# Sensor_Board_v2_4_1_2_N.net
KiCad netlist of a schematic drawn in EAGLE
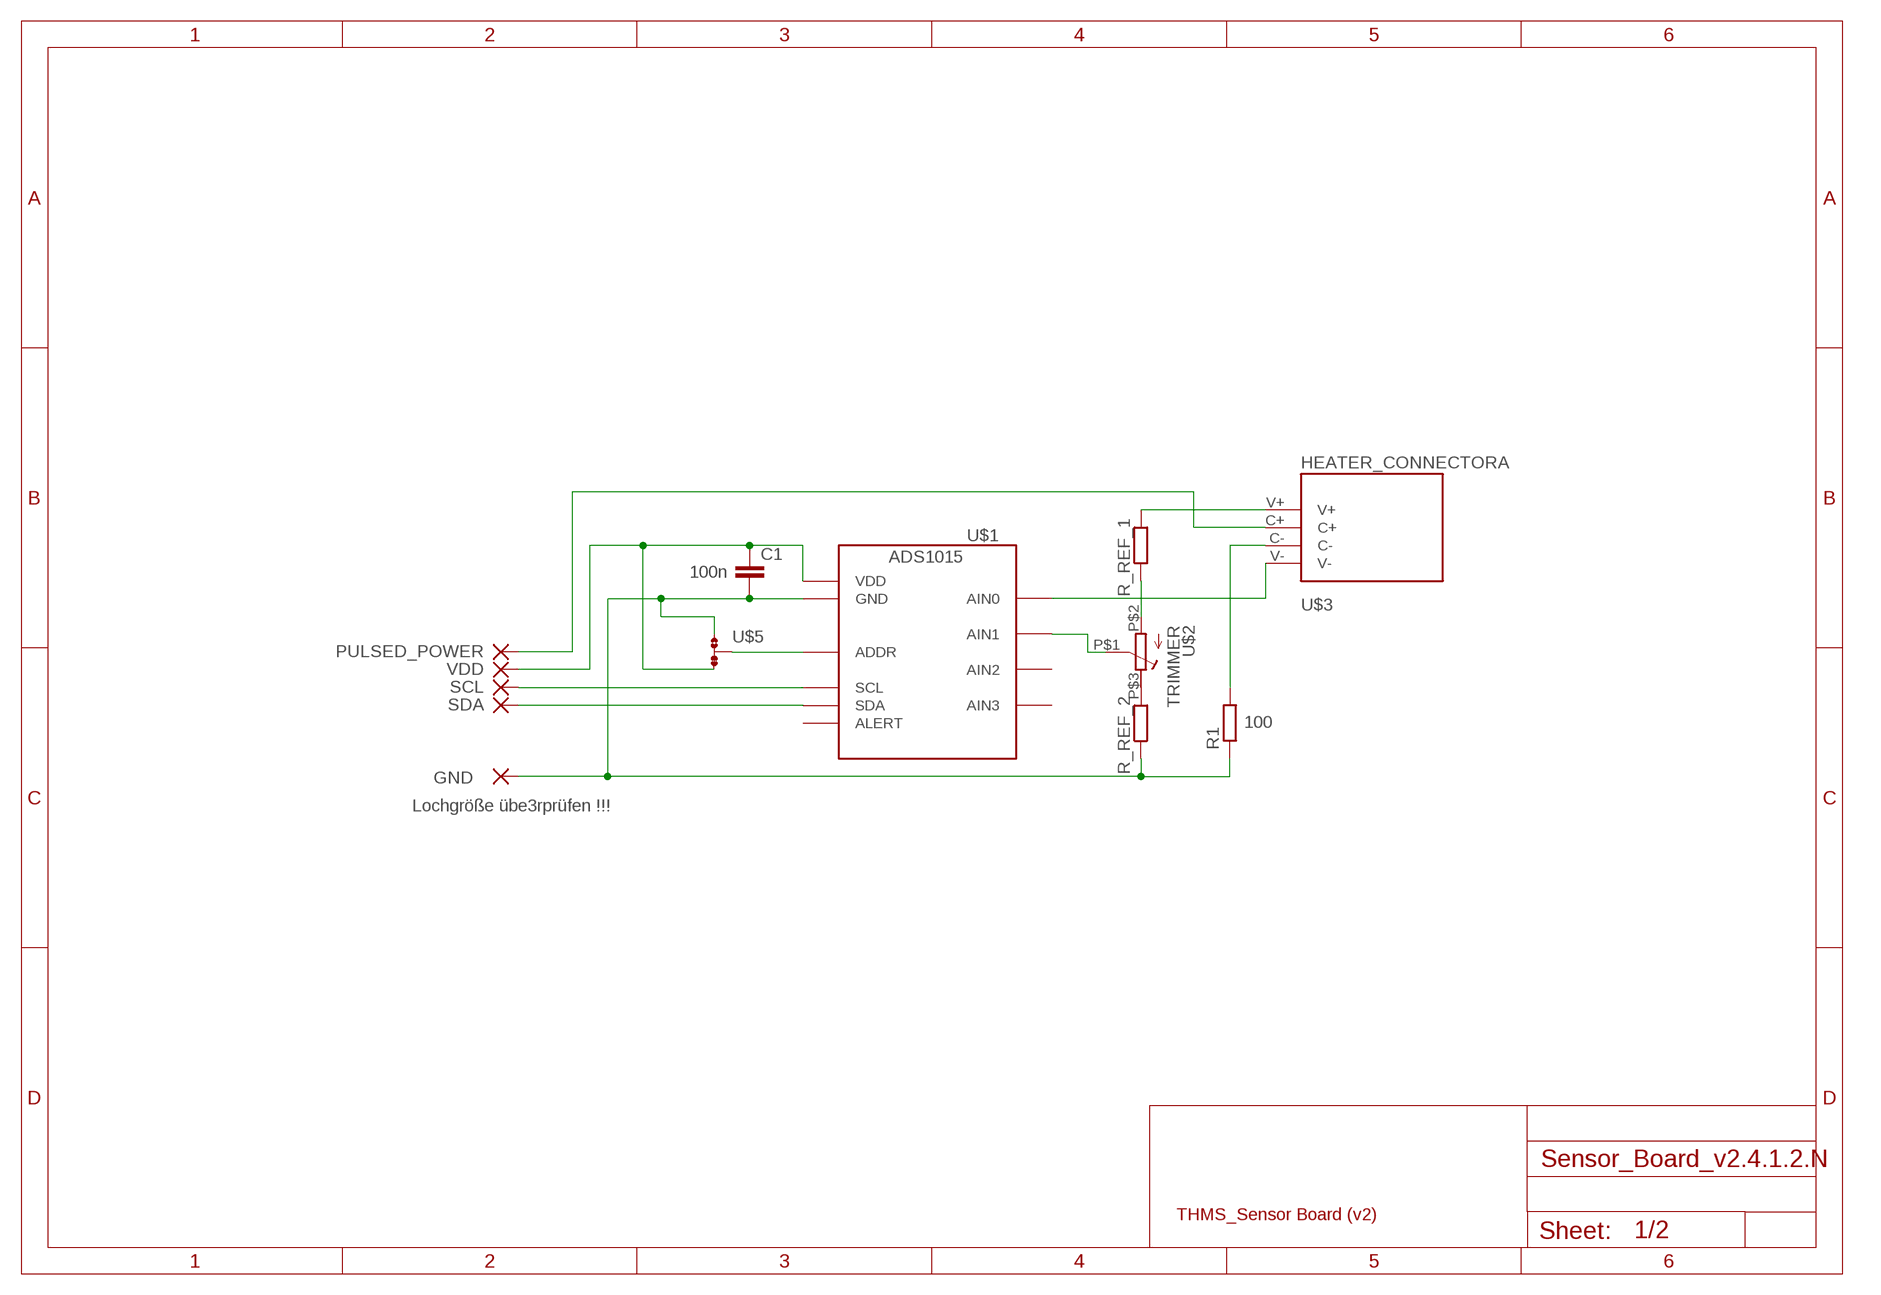
[diagram p0: schematic, sheet 1]
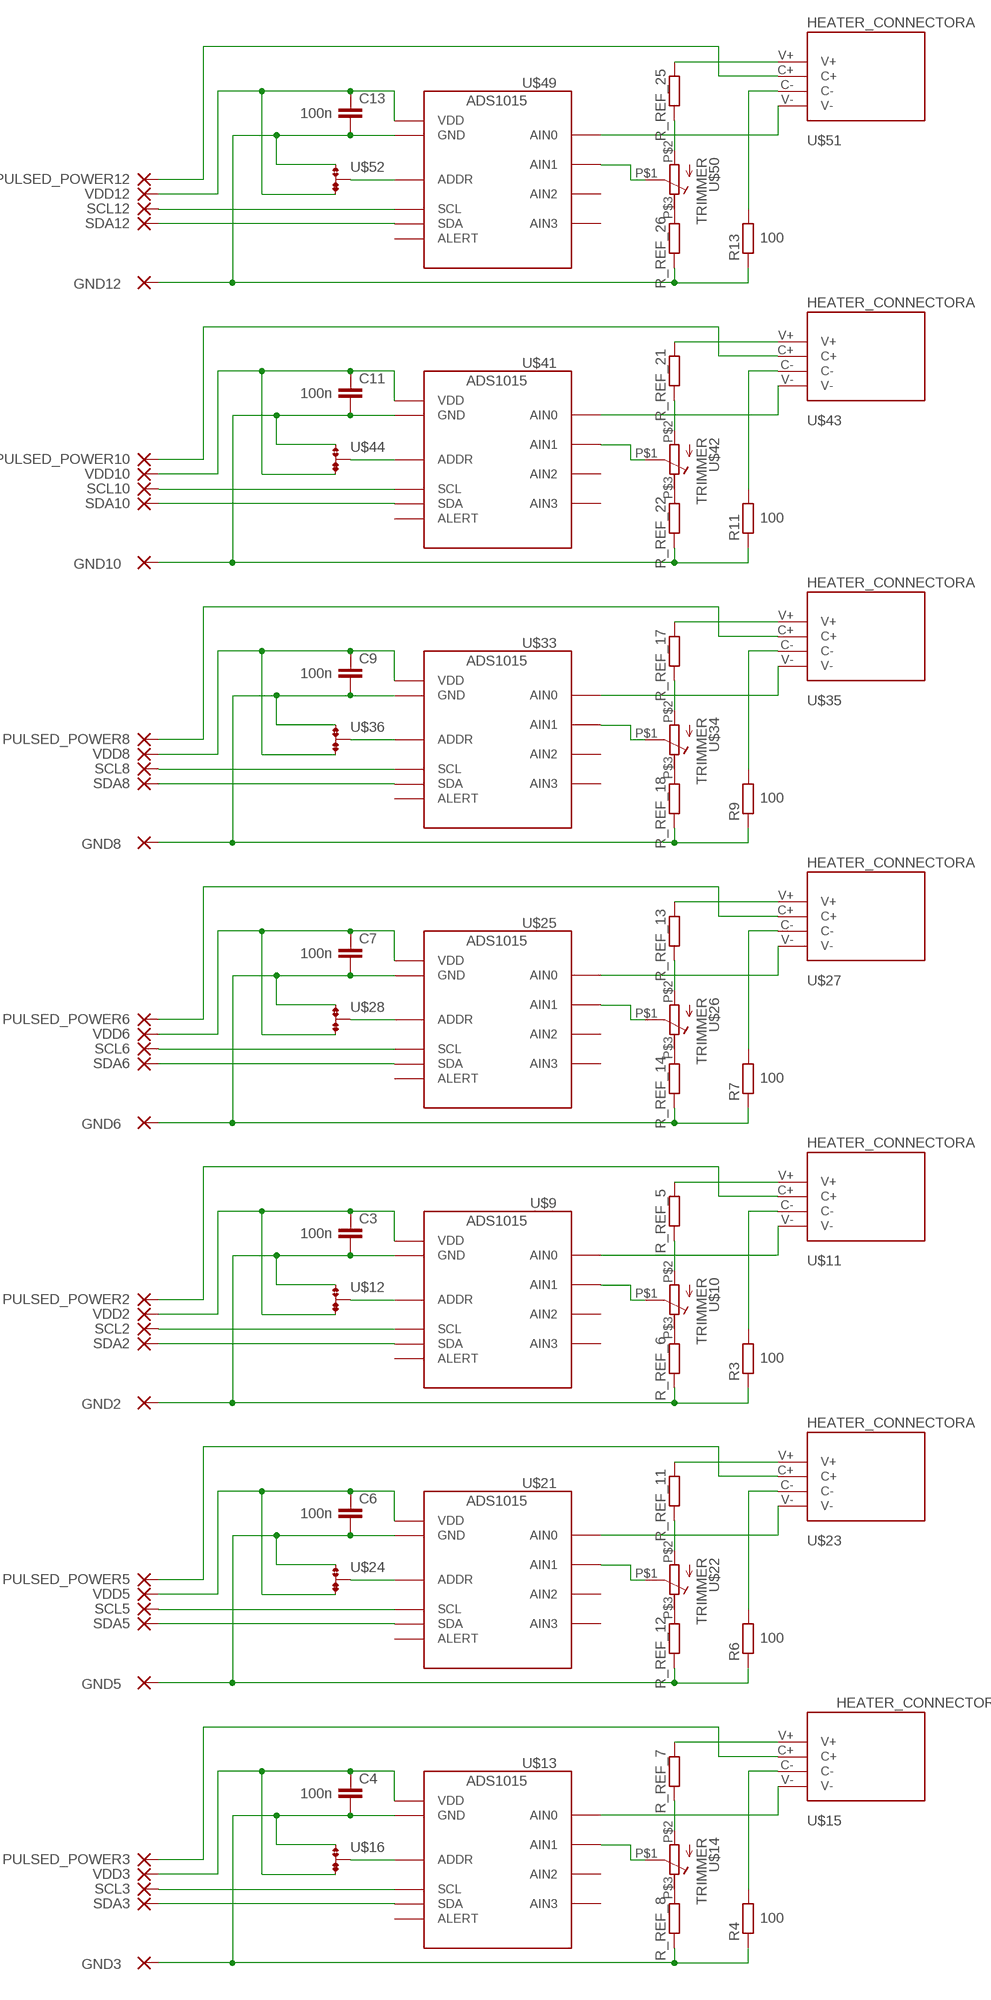
[diagram p1: schematic, sheet 2]

(export (version "E")
  (design (tool "Eeschema 10.0.6"))
  (components
    (comp (ref "C3")
      (value "100n")
      (footprint "eagle-import:C0201")
      (libsource (lib "eagle-import") (part "C-EUC0201"))
    )
    (comp (ref "C4")
      (value "100n")
      (footprint "eagle-import:C0201")
      (libsource (lib "eagle-import") (part "C-EUC0201"))
    )
    (comp (ref "C6")
      (value "100n")
      (footprint "eagle-import:C0201")
      (libsource (lib "eagle-import") (part "C-EUC0201"))
    )
    (comp (ref "C7")
      (value "100n")
      (footprint "eagle-import:C0201")
      (libsource (lib "eagle-import") (part "C-EUC0201"))
    )
    (comp (ref "C9")
      (value "100n")
      (footprint "eagle-import:C0201")
      (libsource (lib "eagle-import") (part "C-EUC0201"))
    )
    (comp (ref "C11")
      (value "100n")
      (footprint "eagle-import:C0201")
      (libsource (lib "eagle-import") (part "C-EUC0201"))
    )
    (comp (ref "C13")
      (value "100n")
      (footprint "eagle-import:C0201")
      (libsource (lib "eagle-import") (part "C-EUC0201"))
    )
    (comp (ref "GND2")
      (value "2,54/1,1")
      (footprint "eagle-import:2,54_1,1")
      (libsource (lib "eagle-import") (part "2,54/1,1"))
    )
    (comp (ref "GND3")
      (value "2,54/1,1")
      (footprint "eagle-import:2,54_1,1")
      (libsource (lib "eagle-import") (part "2,54/1,1"))
    )
    (comp (ref "GND5")
      (value "2,54/1,1")
      (footprint "eagle-import:2,54_1,1")
      (libsource (lib "eagle-import") (part "2,54/1,1"))
    )
    (comp (ref "GND6")
      (value "2,54/1,1")
      (footprint "eagle-import:2,54_1,1")
      (libsource (lib "eagle-import") (part "2,54/1,1"))
    )
    (comp (ref "GND8")
      (value "2,54/1,1")
      (footprint "eagle-import:2,54_1,1")
      (libsource (lib "eagle-import") (part "2,54/1,1"))
    )
    (comp (ref "GND10")
      (value "2,54/1,1")
      (footprint "eagle-import:2,54_1,1")
      (libsource (lib "eagle-import") (part "2,54/1,1"))
    )
    (comp (ref "GND12")
      (value "2,54/1,1")
      (footprint "eagle-import:2,54_1,1")
      (libsource (lib "eagle-import") (part "2,54/1,1"))
    )
    (comp (ref "PULSED_POWER2")
      (value "SMD_PADSMD05-2(STPOO_DEFINED)")
      (footprint "eagle-import:SMD0,5-2(STOP_DEFINED)")
      (libsource (lib "eagle-import") (part "SMD_PADSMD05-2(STPOO_DEFINED)"))
    )
    (comp (ref "PULSED_POWER3")
      (value "SMD_PADSMD05-2(STPOO_DEFINED)")
      (footprint "eagle-import:SMD0,5-2(STOP_DEFINED)")
      (libsource (lib "eagle-import") (part "SMD_PADSMD05-2(STPOO_DEFINED)"))
    )
    (comp (ref "PULSED_POWER5")
      (value "SMD_PADSMD05-2(STPOO_DEFINED)")
      (footprint "eagle-import:SMD0,5-2(STOP_DEFINED)")
      (libsource (lib "eagle-import") (part "SMD_PADSMD05-2(STPOO_DEFINED)"))
    )
    (comp (ref "PULSED_POWER6")
      (value "SMD_PADSMD05-2(STPOO_DEFINED)")
      (footprint "eagle-import:SMD0,5-2(STOP_DEFINED)")
      (libsource (lib "eagle-import") (part "SMD_PADSMD05-2(STPOO_DEFINED)"))
    )
    (comp (ref "PULSED_POWER8")
      (value "SMD_PADSMD05-2(STPOO_DEFINED)")
      (footprint "eagle-import:SMD0,5-2(STOP_DEFINED)")
      (libsource (lib "eagle-import") (part "SMD_PADSMD05-2(STPOO_DEFINED)"))
    )
    (comp (ref "PULSED_POWER10")
      (value "SMD_PADSMD05-2(STPOO_DEFINED)")
      (footprint "eagle-import:SMD0,5-2(STOP_DEFINED)")
      (libsource (lib "eagle-import") (part "SMD_PADSMD05-2(STPOO_DEFINED)"))
    )
    (comp (ref "PULSED_POWER12")
      (value "SMD_PADSMD05-2(STPOO_DEFINED)")
      (footprint "eagle-import:SMD0,5-2(STOP_DEFINED)")
      (libsource (lib "eagle-import") (part "SMD_PADSMD05-2(STPOO_DEFINED)"))
    )
    (comp (ref "R3")
      (value "100")
      (footprint "eagle-import:R0402")
      (libsource (lib "eagle-import") (part "R-EU_R0402"))
    )
    (comp (ref "R4")
      (value "100")
      (footprint "eagle-import:R0402")
      (libsource (lib "eagle-import") (part "R-EU_R0402"))
    )
    (comp (ref "R6")
      (value "100")
      (footprint "eagle-import:R0402")
      (libsource (lib "eagle-import") (part "R-EU_R0402"))
    )
    (comp (ref "R7")
      (value "100")
      (footprint "eagle-import:R0402")
      (libsource (lib "eagle-import") (part "R-EU_R0402"))
    )
    (comp (ref "R9")
      (value "100")
      (footprint "eagle-import:R0402")
      (libsource (lib "eagle-import") (part "R-EU_R0402"))
    )
    (comp (ref "R11")
      (value "100")
      (footprint "eagle-import:R0402")
      (libsource (lib "eagle-import") (part "R-EU_R0402"))
    )
    (comp (ref "R13")
      (value "100")
      (footprint "eagle-import:R0402")
      (libsource (lib "eagle-import") (part "R-EU_R0402"))
    )
    (comp (ref "R_REF_5")
      (value "0")
      (footprint "eagle-import:R0201")
      (libsource (lib "eagle-import") (part "R-EU_R0201"))
    )
    (comp (ref "R_REF_6")
      (value "0")
      (footprint "eagle-import:R0201")
      (libsource (lib "eagle-import") (part "R-EU_R0201"))
    )
    (comp (ref "R_REF_7")
      (value "0")
      (footprint "eagle-import:R0201")
      (libsource (lib "eagle-import") (part "R-EU_R0201"))
    )
    (comp (ref "R_REF_8")
      (value "0")
      (footprint "eagle-import:R0201")
      (libsource (lib "eagle-import") (part "R-EU_R0201"))
    )
    (comp (ref "R_REF_11")
      (value "0")
      (footprint "eagle-import:R0201")
      (libsource (lib "eagle-import") (part "R-EU_R0201"))
    )
    (comp (ref "R_REF_12")
      (value "0")
      (footprint "eagle-import:R0201")
      (libsource (lib "eagle-import") (part "R-EU_R0201"))
    )
    (comp (ref "R_REF_13")
      (value "0")
      (footprint "eagle-import:R0201")
      (libsource (lib "eagle-import") (part "R-EU_R0201"))
    )
    (comp (ref "R_REF_14")
      (value "0")
      (footprint "eagle-import:R0201")
      (libsource (lib "eagle-import") (part "R-EU_R0201"))
    )
    (comp (ref "R_REF_17")
      (value "0")
      (footprint "eagle-import:R0201")
      (libsource (lib "eagle-import") (part "R-EU_R0201"))
    )
    (comp (ref "R_REF_18")
      (value "0")
      (footprint "eagle-import:R0201")
      (libsource (lib "eagle-import") (part "R-EU_R0201"))
    )
    (comp (ref "R_REF_21")
      (value "0")
      (footprint "eagle-import:R0201")
      (libsource (lib "eagle-import") (part "R-EU_R0201"))
    )
    (comp (ref "R_REF_22")
      (value "0")
      (footprint "eagle-import:R0201")
      (libsource (lib "eagle-import") (part "R-EU_R0201"))
    )
    (comp (ref "R_REF_25")
      (value "0")
      (footprint "eagle-import:R0201")
      (libsource (lib "eagle-import") (part "R-EU_R0201"))
    )
    (comp (ref "R_REF_26")
      (value "0")
      (footprint "eagle-import:R0201")
      (libsource (lib "eagle-import") (part "R-EU_R0201"))
    )
    (comp (ref "SCL2")
      (value "SMD_PADSMD05-2(STPOO_DEFINED)")
      (footprint "eagle-import:SMD0,5-2(STOP_DEFINED)")
      (libsource (lib "eagle-import") (part "SMD_PADSMD05-2(STPOO_DEFINED)"))
    )
    (comp (ref "SCL3")
      (value "SMD_PADSMD05-2(STPOO_DEFINED)")
      (footprint "eagle-import:SMD0,5-2(STOP_DEFINED)")
      (libsource (lib "eagle-import") (part "SMD_PADSMD05-2(STPOO_DEFINED)"))
    )
    (comp (ref "SCL5")
      (value "SMD_PADSMD05-2(STPOO_DEFINED)")
      (footprint "eagle-import:SMD0,5-2(STOP_DEFINED)")
      (libsource (lib "eagle-import") (part "SMD_PADSMD05-2(STPOO_DEFINED)"))
    )
    (comp (ref "SCL6")
      (value "SMD_PADSMD05-2(STPOO_DEFINED)")
      (footprint "eagle-import:SMD0,5-2(STOP_DEFINED)")
      (libsource (lib "eagle-import") (part "SMD_PADSMD05-2(STPOO_DEFINED)"))
    )
    (comp (ref "SCL8")
      (value "SMD_PADSMD05-2(STPOO_DEFINED)")
      (footprint "eagle-import:SMD0,5-2(STOP_DEFINED)")
      (libsource (lib "eagle-import") (part "SMD_PADSMD05-2(STPOO_DEFINED)"))
    )
    (comp (ref "SCL10")
      (value "SMD_PADSMD05-2(STPOO_DEFINED)")
      (footprint "eagle-import:SMD0,5-2(STOP_DEFINED)")
      (libsource (lib "eagle-import") (part "SMD_PADSMD05-2(STPOO_DEFINED)"))
    )
    (comp (ref "SCL12")
      (value "SMD_PADSMD05-2(STPOO_DEFINED)")
      (footprint "eagle-import:SMD0,5-2(STOP_DEFINED)")
      (libsource (lib "eagle-import") (part "SMD_PADSMD05-2(STPOO_DEFINED)"))
    )
    (comp (ref "SDA2")
      (value "SMD_PADSMD05-2(STPOO_DEFINED)")
      (footprint "eagle-import:SMD0,5-2(STOP_DEFINED)")
      (libsource (lib "eagle-import") (part "SMD_PADSMD05-2(STPOO_DEFINED)"))
    )
    (comp (ref "SDA3")
      (value "SMD_PADSMD05-2(STPOO_DEFINED)")
      (footprint "eagle-import:SMD0,5-2(STOP_DEFINED)")
      (libsource (lib "eagle-import") (part "SMD_PADSMD05-2(STPOO_DEFINED)"))
    )
    (comp (ref "SDA5")
      (value "SMD_PADSMD05-2(STPOO_DEFINED)")
      (footprint "eagle-import:SMD0,5-2(STOP_DEFINED)")
      (libsource (lib "eagle-import") (part "SMD_PADSMD05-2(STPOO_DEFINED)"))
    )
    (comp (ref "SDA6")
      (value "SMD_PADSMD05-2(STPOO_DEFINED)")
      (footprint "eagle-import:SMD0,5-2(STOP_DEFINED)")
      (libsource (lib "eagle-import") (part "SMD_PADSMD05-2(STPOO_DEFINED)"))
    )
    (comp (ref "SDA8")
      (value "SMD_PADSMD05-2(STPOO_DEFINED)")
      (footprint "eagle-import:SMD0,5-2(STOP_DEFINED)")
      (libsource (lib "eagle-import") (part "SMD_PADSMD05-2(STPOO_DEFINED)"))
    )
    (comp (ref "SDA10")
      (value "SMD_PADSMD05-2(STPOO_DEFINED)")
      (footprint "eagle-import:SMD0,5-2(STOP_DEFINED)")
      (libsource (lib "eagle-import") (part "SMD_PADSMD05-2(STPOO_DEFINED)"))
    )
    (comp (ref "SDA12")
      (value "SMD_PADSMD05-2(STPOO_DEFINED)")
      (footprint "eagle-import:SMD0,5-2(STOP_DEFINED)")
      (libsource (lib "eagle-import") (part "SMD_PADSMD05-2(STPOO_DEFINED)"))
    )
    (comp (ref "U$9")
      (value "ADS1015")
      (footprint "eagle-import:X2QFN10")
      (libsource (lib "eagle-import") (part "ADS1015"))
    )
    (comp (ref "U$10")
      (value "TRIMMER")
      (footprint "eagle-import:2MM")
      (libsource (lib "eagle-import") (part "TRIMMER"))
    )
    (comp (ref "U$11")
      (value "HEATER_CONNECTORA")
      (footprint "eagle-import:CONECTION_GATES")
      (libsource (lib "eagle-import") (part "HEATER_CONNECTORA"))
    )
    (comp (ref "U$12")
      (value "0R-JUMP-1CON")
      (footprint "eagle-import:D0R-JMP(D)")
      (libsource (lib "eagle-import") (part "0R-JUMP-1CON"))
    )
    (comp (ref "U$13")
      (value "ADS1015")
      (footprint "eagle-import:X2QFN10")
      (libsource (lib "eagle-import") (part "ADS1015"))
    )
    (comp (ref "U$14")
      (value "TRIMMER")
      (footprint "eagle-import:2MM")
      (libsource (lib "eagle-import") (part "TRIMMER"))
    )
    (comp (ref "U$15")
      (value "HEATER_CONNECTORA")
      (footprint "eagle-import:CONECTION_GATES")
      (libsource (lib "eagle-import") (part "HEATER_CONNECTORA"))
    )
    (comp (ref "U$16")
      (value "0R-JUMP-1CON")
      (footprint "eagle-import:D0R-JMP(D)")
      (libsource (lib "eagle-import") (part "0R-JUMP-1CON"))
    )
    (comp (ref "U$21")
      (value "ADS1015")
      (footprint "eagle-import:X2QFN10")
      (libsource (lib "eagle-import") (part "ADS1015"))
    )
    (comp (ref "U$22")
      (value "TRIMMER")
      (footprint "eagle-import:2MM")
      (libsource (lib "eagle-import") (part "TRIMMER"))
    )
    (comp (ref "U$23")
      (value "HEATER_CONNECTORA")
      (footprint "eagle-import:CONECTION_GATES")
      (libsource (lib "eagle-import") (part "HEATER_CONNECTORA"))
    )
    (comp (ref "U$24")
      (value "0R-JUMP-1CON")
      (footprint "eagle-import:D0R-JMP(D)")
      (libsource (lib "eagle-import") (part "0R-JUMP-1CON"))
    )
    (comp (ref "U$25")
      (value "ADS1015")
      (footprint "eagle-import:X2QFN10")
      (libsource (lib "eagle-import") (part "ADS1015"))
    )
    (comp (ref "U$26")
      (value "TRIMMER")
      (footprint "eagle-import:2MM")
      (libsource (lib "eagle-import") (part "TRIMMER"))
    )
    (comp (ref "U$27")
      (value "HEATER_CONNECTORA")
      (footprint "eagle-import:CONECTION_GATES")
      (libsource (lib "eagle-import") (part "HEATER_CONNECTORA"))
    )
    (comp (ref "U$28")
      (value "0R-JUMP-1CON")
      (footprint "eagle-import:D0R-JMP(D)")
      (libsource (lib "eagle-import") (part "0R-JUMP-1CON"))
    )
    (comp (ref "U$33")
      (value "ADS1015")
      (footprint "eagle-import:X2QFN10")
      (libsource (lib "eagle-import") (part "ADS1015"))
    )
    (comp (ref "U$34")
      (value "TRIMMER")
      (footprint "eagle-import:2MM")
      (libsource (lib "eagle-import") (part "TRIMMER"))
    )
    (comp (ref "U$35")
      (value "HEATER_CONNECTORA")
      (footprint "eagle-import:CONECTION_GATES")
      (libsource (lib "eagle-import") (part "HEATER_CONNECTORA"))
    )
    (comp (ref "U$36")
      (value "0R-JUMP-1CON")
      (footprint "eagle-import:D0R-JMP(D)")
      (libsource (lib "eagle-import") (part "0R-JUMP-1CON"))
    )
    (comp (ref "U$41")
      (value "ADS1015")
      (footprint "eagle-import:X2QFN10")
      (libsource (lib "eagle-import") (part "ADS1015"))
    )
    (comp (ref "U$42")
      (value "TRIMMER")
      (footprint "eagle-import:2MM")
      (libsource (lib "eagle-import") (part "TRIMMER"))
    )
    (comp (ref "U$43")
      (value "HEATER_CONNECTORA")
      (footprint "eagle-import:CONECTION_GATES")
      (libsource (lib "eagle-import") (part "HEATER_CONNECTORA"))
    )
    (comp (ref "U$44")
      (value "0R-JUMP-1CON")
      (footprint "eagle-import:D0R-JMP(D)")
      (libsource (lib "eagle-import") (part "0R-JUMP-1CON"))
    )
    (comp (ref "U$49")
      (value "ADS1015")
      (footprint "eagle-import:X2QFN10")
      (libsource (lib "eagle-import") (part "ADS1015"))
    )
    (comp (ref "U$50")
      (value "TRIMMER")
      (footprint "eagle-import:2MM")
      (libsource (lib "eagle-import") (part "TRIMMER"))
    )
    (comp (ref "U$51")
      (value "HEATER_CONNECTORA")
      (footprint "eagle-import:CONECTION_GATES")
      (libsource (lib "eagle-import") (part "HEATER_CONNECTORA"))
    )
    (comp (ref "U$52")
      (value "0R-JUMP-1CON")
      (footprint "eagle-import:D0R-JMP(D)")
      (libsource (lib "eagle-import") (part "0R-JUMP-1CON"))
    )
    (comp (ref "VDD2")
      (value "SMD_PADSMD05-2(STPOO_DEFINED)")
      (footprint "eagle-import:SMD0,5-2(STOP_DEFINED)")
      (libsource (lib "eagle-import") (part "SMD_PADSMD05-2(STPOO_DEFINED)"))
    )
    (comp (ref "VDD3")
      (value "SMD_PADSMD05-2(STPOO_DEFINED)")
      (footprint "eagle-import:SMD0,5-2(STOP_DEFINED)")
      (libsource (lib "eagle-import") (part "SMD_PADSMD05-2(STPOO_DEFINED)"))
    )
    (comp (ref "VDD5")
      (value "SMD_PADSMD05-2(STPOO_DEFINED)")
      (footprint "eagle-import:SMD0,5-2(STOP_DEFINED)")
      (libsource (lib "eagle-import") (part "SMD_PADSMD05-2(STPOO_DEFINED)"))
    )
    (comp (ref "VDD6")
      (value "SMD_PADSMD05-2(STPOO_DEFINED)")
      (footprint "eagle-import:SMD0,5-2(STOP_DEFINED)")
      (libsource (lib "eagle-import") (part "SMD_PADSMD05-2(STPOO_DEFINED)"))
    )
    (comp (ref "VDD8")
      (value "SMD_PADSMD05-2(STPOO_DEFINED)")
      (footprint "eagle-import:SMD0,5-2(STOP_DEFINED)")
      (libsource (lib "eagle-import") (part "SMD_PADSMD05-2(STPOO_DEFINED)"))
    )
    (comp (ref "VDD10")
      (value "SMD_PADSMD05-2(STPOO_DEFINED)")
      (footprint "eagle-import:SMD0,5-2(STOP_DEFINED)")
      (libsource (lib "eagle-import") (part "SMD_PADSMD05-2(STPOO_DEFINED)"))
    )
    (comp (ref "VDD12")
      (value "SMD_PADSMD05-2(STPOO_DEFINED)")
      (footprint "eagle-import:SMD0,5-2(STOP_DEFINED)")
      (libsource (lib "eagle-import") (part "SMD_PADSMD05-2(STPOO_DEFINED)"))
    )
    (comp (ref "C1")
      (value "100n")
      (footprint "eagle-import:C0201")
      (libsource (lib "eagle-import") (part "C-EUC0201"))
    )
    (comp (ref "GND")
      (value "2,54/1,1")
      (footprint "eagle-import:2,54_1,1")
      (libsource (lib "eagle-import") (part "2,54/1,1"))
    )
    (comp (ref "PULSED_POWER")
      (value "SMD_PADSMD05-2(STPOO_DEFINED)")
      (footprint "eagle-import:SMD0,5-2(STOP_DEFINED)")
      (libsource (lib "eagle-import") (part "SMD_PADSMD05-2(STPOO_DEFINED)"))
    )
    (comp (ref "R1")
      (value "100")
      (footprint "eagle-import:R0402")
      (libsource (lib "eagle-import") (part "R-EU_R0402"))
    )
    (comp (ref "R_REF_1")
      (value "0")
      (footprint "eagle-import:R0201")
      (libsource (lib "eagle-import") (part "R-EU_R0201"))
    )
    (comp (ref "R_REF_2")
      (value "0")
      (footprint "eagle-import:R0201")
      (libsource (lib "eagle-import") (part "R-EU_R0201"))
    )
    (comp (ref "SCL")
      (value "SMD_PADSMD05-2(STPOO_DEFINED)")
      (footprint "eagle-import:SMD0,5-2(STOP_DEFINED)")
      (libsource (lib "eagle-import") (part "SMD_PADSMD05-2(STPOO_DEFINED)"))
    )
    (comp (ref "SDA")
      (value "SMD_PADSMD05-2(STPOO_DEFINED)")
      (footprint "eagle-import:SMD0,5-2(STOP_DEFINED)")
      (libsource (lib "eagle-import") (part "SMD_PADSMD05-2(STPOO_DEFINED)"))
    )
    (comp (ref "U$1")
      (value "ADS1015")
      (footprint "eagle-import:X2QFN10")
      (libsource (lib "eagle-import") (part "ADS1015"))
    )
    (comp (ref "U$2")
      (value "TRIMMER")
      (footprint "eagle-import:2MM")
      (libsource (lib "eagle-import") (part "TRIMMER"))
    )
    (comp (ref "U$3")
      (value "HEATER_CONNECTORA")
      (footprint "eagle-import:CONECTION_GATES")
      (libsource (lib "eagle-import") (part "HEATER_CONNECTORA"))
    )
    (comp (ref "U$5")
      (value "0R-JUMP-1CON")
      (footprint "eagle-import:D0R-JMP(D)")
      (libsource (lib "eagle-import") (part "0R-JUMP-1CON"))
    )
    (comp (ref "VDD")
      (value "SMD_PADSMD05-2(STPOO_DEFINED)")
      (footprint "eagle-import:SMD0,5-2(STOP_DEFINED)")
      (libsource (lib "eagle-import") (part "SMD_PADSMD05-2(STPOO_DEFINED)"))
    )
  )
  (nets
    (net (code "1") (name "GND") (class "Default")
      (node (ref "C1") (pin "2") (pinfunction "2_2") (pintype "passive"))
      (node (ref "C11") (pin "2") (pinfunction "2_2") (pintype "passive"))
      (node (ref "C13") (pin "2") (pinfunction "2_2") (pintype "passive"))
      (node (ref "C3") (pin "2") (pinfunction "2_2") (pintype "passive"))
      (node (ref "C4") (pin "2") (pinfunction "2_2") (pintype "passive"))
      (node (ref "C6") (pin "2") (pinfunction "2_2") (pintype "passive"))
      (node (ref "C7") (pin "2") (pinfunction "2_2") (pintype "passive"))
      (node (ref "C9") (pin "2") (pinfunction "2_2") (pintype "passive"))
      (node (ref "GND") (pin "1") (pinfunction "P_1") (pintype "passive"))
      (node (ref "GND10") (pin "1") (pinfunction "P_1") (pintype "passive"))
      (node (ref "GND12") (pin "1") (pinfunction "P_1") (pintype "passive"))
      (node (ref "GND2") (pin "1") (pinfunction "P_1") (pintype "passive"))
      (node (ref "GND3") (pin "1") (pinfunction "P_1") (pintype "passive"))
      (node (ref "GND5") (pin "1") (pinfunction "P_1") (pintype "passive"))
      (node (ref "GND6") (pin "1") (pinfunction "P_1") (pintype "passive"))
      (node (ref "GND8") (pin "1") (pinfunction "P_1") (pintype "passive"))
      (node (ref "R1") (pin "1") (pinfunction "1_1") (pintype "passive"))
      (node (ref "R11") (pin "1") (pinfunction "1_1") (pintype "passive"))
      (node (ref "R13") (pin "1") (pinfunction "1_1") (pintype "passive"))
      (node (ref "R3") (pin "1") (pinfunction "1_1") (pintype "passive"))
      (node (ref "R4") (pin "1") (pinfunction "1_1") (pintype "passive"))
      (node (ref "R6") (pin "1") (pinfunction "1_1") (pintype "passive"))
      (node (ref "R7") (pin "1") (pinfunction "1_1") (pintype "passive"))
      (node (ref "R9") (pin "1") (pinfunction "1_1") (pintype "passive"))
      (node (ref "R_REF_12") (pin "1") (pinfunction "1_1") (pintype "passive"))
      (node (ref "R_REF_14") (pin "1") (pinfunction "1_1") (pintype "passive"))
      (node (ref "R_REF_18") (pin "1") (pinfunction "1_1") (pintype "passive"))
      (node (ref "R_REF_2") (pin "1") (pinfunction "1_1") (pintype "passive"))
      (node (ref "R_REF_22") (pin "1") (pinfunction "1_1") (pintype "passive"))
      (node (ref "R_REF_26") (pin "1") (pinfunction "1_1") (pintype "passive"))
      (node (ref "R_REF_6") (pin "1") (pinfunction "1_1") (pintype "passive"))
      (node (ref "R_REF_8") (pin "1") (pinfunction "1_1") (pintype "passive"))
      (node (ref "U$1") (pin "P$3") (pinfunction "GND_P$3") (pintype "power_in"))
      (node (ref "U$12") (pin "1") (pinfunction "1_1") (pintype "passive"))
      (node (ref "U$13") (pin "P$3") (pinfunction "GND_P$3") (pintype "power_in"))
      (node (ref "U$16") (pin "1") (pinfunction "1_1") (pintype "passive"))
      (node (ref "U$21") (pin "P$3") (pinfunction "GND_P$3") (pintype "power_in"))
      (node (ref "U$24") (pin "1") (pinfunction "1_1") (pintype "passive"))
      (node (ref "U$25") (pin "P$3") (pinfunction "GND_P$3") (pintype "power_in"))
      (node (ref "U$28") (pin "1") (pinfunction "1_1") (pintype "passive"))
      (node (ref "U$33") (pin "P$3") (pinfunction "GND_P$3") (pintype "power_in"))
      (node (ref "U$36") (pin "1") (pinfunction "1_1") (pintype "passive"))
      (node (ref "U$41") (pin "P$3") (pinfunction "GND_P$3") (pintype "power_in"))
      (node (ref "U$44") (pin "1") (pinfunction "1_1") (pintype "passive"))
      (node (ref "U$49") (pin "P$3") (pinfunction "GND_P$3") (pintype "power_in"))
      (node (ref "U$5") (pin "1") (pinfunction "1_1") (pintype "passive"))
      (node (ref "U$52") (pin "1") (pinfunction "1_1") (pintype "passive"))
      (node (ref "U$9") (pin "P$3") (pinfunction "GND_P$3") (pintype "power_in"))
    )
    (net (code "2") (name "Net-(PULSED_POWER-P)") (class "Default")
      (node (ref "PULSED_POWER") (pin "1") (pinfunction "P_1") (pintype "passive"))
      (node (ref "U$3") (pin "C+") (pinfunction "C+_C+") (pintype "bidirectional"))
    )
    (net (code "3") (name "Net-(PULSED_POWER2-P)") (class "Default")
      (node (ref "PULSED_POWER2") (pin "1") (pinfunction "P_1") (pintype "passive"))
      (node (ref "U$11") (pin "C+") (pinfunction "C+_C+") (pintype "bidirectional"))
    )
    (net (code "4") (name "Net-(PULSED_POWER3-P)") (class "Default")
      (node (ref "PULSED_POWER3") (pin "1") (pinfunction "P_1") (pintype "passive"))
      (node (ref "U$15") (pin "C+") (pinfunction "C+_C+") (pintype "bidirectional"))
    )
    (net (code "5") (name "Net-(PULSED_POWER5-P)") (class "Default")
      (node (ref "PULSED_POWER5") (pin "1") (pinfunction "P_1") (pintype "passive"))
      (node (ref "U$23") (pin "C+") (pinfunction "C+_C+") (pintype "bidirectional"))
    )
    (net (code "6") (name "Net-(PULSED_POWER6-P)") (class "Default")
      (node (ref "PULSED_POWER6") (pin "1") (pinfunction "P_1") (pintype "passive"))
      (node (ref "U$27") (pin "C+") (pinfunction "C+_C+") (pintype "bidirectional"))
    )
    (net (code "7") (name "Net-(PULSED_POWER8-P)") (class "Default")
      (node (ref "PULSED_POWER8") (pin "1") (pinfunction "P_1") (pintype "passive"))
      (node (ref "U$35") (pin "C+") (pinfunction "C+_C+") (pintype "bidirectional"))
    )
    (net (code "8") (name "Net-(PULSED_POWER10-P)") (class "Default")
      (node (ref "PULSED_POWER10") (pin "1") (pinfunction "P_1") (pintype "passive"))
      (node (ref "U$43") (pin "C+") (pinfunction "C+_C+") (pintype "bidirectional"))
    )
    (net (code "9") (name "Net-(PULSED_POWER12-P)") (class "Default")
      (node (ref "PULSED_POWER12") (pin "1") (pinfunction "P_1") (pintype "passive"))
      (node (ref "U$51") (pin "C+") (pinfunction "C+_C+") (pintype "bidirectional"))
    )
    (net (code "10") (name "Net-(R1-Pad2)") (class "Default")
      (node (ref "R1") (pin "2") (pinfunction "2_2") (pintype "passive"))
      (node (ref "U$3") (pin "C-") (pinfunction "C-_C-") (pintype "bidirectional"))
    )
    (net (code "11") (name "Net-(R3-Pad2)") (class "Default")
      (node (ref "R3") (pin "2") (pinfunction "2_2") (pintype "passive"))
      (node (ref "U$11") (pin "C-") (pinfunction "C-_C-") (pintype "bidirectional"))
    )
    (net (code "12") (name "Net-(R4-Pad2)") (class "Default")
      (node (ref "R4") (pin "2") (pinfunction "2_2") (pintype "passive"))
      (node (ref "U$15") (pin "C-") (pinfunction "C-_C-") (pintype "bidirectional"))
    )
    (net (code "13") (name "Net-(R6-Pad2)") (class "Default")
      (node (ref "R6") (pin "2") (pinfunction "2_2") (pintype "passive"))
      (node (ref "U$23") (pin "C-") (pinfunction "C-_C-") (pintype "bidirectional"))
    )
    (net (code "14") (name "Net-(R7-Pad2)") (class "Default")
      (node (ref "R7") (pin "2") (pinfunction "2_2") (pintype "passive"))
      (node (ref "U$27") (pin "C-") (pinfunction "C-_C-") (pintype "bidirectional"))
    )
    (net (code "15") (name "Net-(R9-Pad2)") (class "Default")
      (node (ref "R9") (pin "2") (pinfunction "2_2") (pintype "passive"))
      (node (ref "U$35") (pin "C-") (pinfunction "C-_C-") (pintype "bidirectional"))
    )
    (net (code "16") (name "Net-(R11-Pad2)") (class "Default")
      (node (ref "R11") (pin "2") (pinfunction "2_2") (pintype "passive"))
      (node (ref "U$43") (pin "C-") (pinfunction "C-_C-") (pintype "bidirectional"))
    )
    (net (code "17") (name "Net-(R13-Pad2)") (class "Default")
      (node (ref "R13") (pin "2") (pinfunction "2_2") (pintype "passive"))
      (node (ref "U$51") (pin "C-") (pinfunction "C-_C-") (pintype "bidirectional"))
    )
    (net (code "18") (name "Net-(R_REF_1-Pad2)") (class "Default")
      (node (ref "R_REF_1") (pin "2") (pinfunction "2_2") (pintype "passive"))
      (node (ref "U$3") (pin "V+") (pinfunction "V+_V+") (pintype "bidirectional"))
    )
    (net (code "19") (name "Net-(R_REF_5-Pad2)") (class "Default")
      (node (ref "R_REF_5") (pin "2") (pinfunction "2_2") (pintype "passive"))
      (node (ref "U$11") (pin "V+") (pinfunction "V+_V+") (pintype "bidirectional"))
    )
    (net (code "20") (name "Net-(R_REF_7-Pad2)") (class "Default")
      (node (ref "R_REF_7") (pin "2") (pinfunction "2_2") (pintype "passive"))
      (node (ref "U$15") (pin "V+") (pinfunction "V+_V+") (pintype "bidirectional"))
    )
    (net (code "21") (name "Net-(R_REF_11-Pad2)") (class "Default")
      (node (ref "R_REF_11") (pin "2") (pinfunction "2_2") (pintype "passive"))
      (node (ref "U$23") (pin "V+") (pinfunction "V+_V+") (pintype "bidirectional"))
    )
    (net (code "22") (name "Net-(R_REF_13-Pad2)") (class "Default")
      (node (ref "R_REF_13") (pin "2") (pinfunction "2_2") (pintype "passive"))
      (node (ref "U$27") (pin "V+") (pinfunction "V+_V+") (pintype "bidirectional"))
    )
    (net (code "23") (name "Net-(R_REF_17-Pad2)") (class "Default")
      (node (ref "R_REF_17") (pin "2") (pinfunction "2_2") (pintype "passive"))
      (node (ref "U$35") (pin "V+") (pinfunction "V+_V+") (pintype "bidirectional"))
    )
    (net (code "24") (name "Net-(R_REF_21-Pad2)") (class "Default")
      (node (ref "R_REF_21") (pin "2") (pinfunction "2_2") (pintype "passive"))
      (node (ref "U$43") (pin "V+") (pinfunction "V+_V+") (pintype "bidirectional"))
    )
    (net (code "25") (name "Net-(R_REF_25-Pad2)") (class "Default")
      (node (ref "R_REF_25") (pin "2") (pinfunction "2_2") (pintype "passive"))
      (node (ref "U$51") (pin "V+") (pinfunction "V+_V+") (pintype "bidirectional"))
    )
    (net (code "26") (name "Net-(SCL-P)") (class "Default")
      (node (ref "SCL") (pin "1") (pinfunction "P_1") (pintype "passive"))
      (node (ref "U$1") (pin "P$10") (pinfunction "SCL_P$10") (pintype "bidirectional"))
    )
    (net (code "27") (name "Net-(SCL2-P)") (class "Default")
      (node (ref "SCL2") (pin "1") (pinfunction "P_1") (pintype "passive"))
      (node (ref "U$9") (pin "P$10") (pinfunction "SCL_P$10") (pintype "bidirectional"))
    )
    (net (code "28") (name "Net-(SCL3-P)") (class "Default")
      (node (ref "SCL3") (pin "1") (pinfunction "P_1") (pintype "passive"))
      (node (ref "U$13") (pin "P$10") (pinfunction "SCL_P$10") (pintype "bidirectional"))
    )
    (net (code "29") (name "Net-(SCL5-P)") (class "Default")
      (node (ref "SCL5") (pin "1") (pinfunction "P_1") (pintype "passive"))
      (node (ref "U$21") (pin "P$10") (pinfunction "SCL_P$10") (pintype "bidirectional"))
    )
    (net (code "30") (name "Net-(SCL6-P)") (class "Default")
      (node (ref "SCL6") (pin "1") (pinfunction "P_1") (pintype "passive"))
      (node (ref "U$25") (pin "P$10") (pinfunction "SCL_P$10") (pintype "bidirectional"))
    )
    (net (code "31") (name "Net-(SCL8-P)") (class "Default")
      (node (ref "SCL8") (pin "1") (pinfunction "P_1") (pintype "passive"))
      (node (ref "U$33") (pin "P$10") (pinfunction "SCL_P$10") (pintype "bidirectional"))
    )
    (net (code "32") (name "Net-(SCL10-P)") (class "Default")
      (node (ref "SCL10") (pin "1") (pinfunction "P_1") (pintype "passive"))
      (node (ref "U$41") (pin "P$10") (pinfunction "SCL_P$10") (pintype "bidirectional"))
    )
    (net (code "33") (name "Net-(SCL12-P)") (class "Default")
      (node (ref "SCL12") (pin "1") (pinfunction "P_1") (pintype "passive"))
      (node (ref "U$49") (pin "P$10") (pinfunction "SCL_P$10") (pintype "bidirectional"))
    )
    (net (code "34") (name "Net-(SDA-P)") (class "Default")
      (node (ref "SDA") (pin "1") (pinfunction "P_1") (pintype "passive"))
      (node (ref "U$1") (pin "P$9") (pinfunction "SDA_P$9") (pintype "bidirectional"))
    )
    (net (code "35") (name "Net-(SDA2-P)") (class "Default")
      (node (ref "SDA2") (pin "1") (pinfunction "P_1") (pintype "passive"))
      (node (ref "U$9") (pin "P$9") (pinfunction "SDA_P$9") (pintype "bidirectional"))
    )
    (net (code "36") (name "Net-(SDA3-P)") (class "Default")
      (node (ref "SDA3") (pin "1") (pinfunction "P_1") (pintype "passive"))
      (node (ref "U$13") (pin "P$9") (pinfunction "SDA_P$9") (pintype "bidirectional"))
    )
    (net (code "37") (name "Net-(SDA5-P)") (class "Default")
      (node (ref "SDA5") (pin "1") (pinfunction "P_1") (pintype "passive"))
      (node (ref "U$21") (pin "P$9") (pinfunction "SDA_P$9") (pintype "bidirectional"))
    )
    (net (code "38") (name "Net-(SDA6-P)") (class "Default")
      (node (ref "SDA6") (pin "1") (pinfunction "P_1") (pintype "passive"))
      (node (ref "U$25") (pin "P$9") (pinfunction "SDA_P$9") (pintype "bidirectional"))
    )
    (net (code "39") (name "Net-(SDA8-P)") (class "Default")
      (node (ref "SDA8") (pin "1") (pinfunction "P_1") (pintype "passive"))
      (node (ref "U$33") (pin "P$9") (pinfunction "SDA_P$9") (pintype "bidirectional"))
    )
    (net (code "40") (name "Net-(SDA10-P)") (class "Default")
      (node (ref "SDA10") (pin "1") (pinfunction "P_1") (pintype "passive"))
      (node (ref "U$41") (pin "P$9") (pinfunction "SDA_P$9") (pintype "bidirectional"))
    )
    (net (code "41") (name "Net-(SDA12-P)") (class "Default")
      (node (ref "SDA12") (pin "1") (pinfunction "P_1") (pintype "passive"))
      (node (ref "U$49") (pin "P$9") (pinfunction "SDA_P$9") (pintype "bidirectional"))
    )
    (net (code "42") (name "Net-(U$1-ADDR)") (class "Default")
      (node (ref "U$1") (pin "P$1") (pinfunction "ADDR_P$1") (pintype "input"))
      (node (ref "U$5") (pin "2") (pinfunction "2_2") (pintype "passive"))
    )
    (net (code "43") (name "Net-(U$1-AIN0)") (class "Default")
      (node (ref "U$1") (pin "P$4") (pinfunction "AIN0_P$4") (pintype "input"))
      (node (ref "U$3") (pin "V-") (pinfunction "V-_V-") (pintype "bidirectional"))
    )
    (net (code "44") (name "Net-(U$1-AIN1)") (class "Default")
      (node (ref "U$1") (pin "P$5") (pinfunction "AIN1_P$5") (pintype "input"))
      (node (ref "U$2") (pin "P$1") (pinfunction "S_P$1") (pintype "passive"))
    )
    (net (code "45") (name "Net-(U$2-A)") (class "Default")
      (node (ref "R_REF_2") (pin "2") (pinfunction "2_2") (pintype "passive"))
      (node (ref "U$2") (pin "P$3") (pinfunction "A_P$3") (pintype "passive"))
    )
    (net (code "46") (name "Net-(U$2-E)") (class "Default")
      (node (ref "R_REF_1") (pin "1") (pinfunction "1_1") (pintype "passive"))
      (node (ref "U$2") (pin "P$2") (pinfunction "E_P$2") (pintype "passive"))
    )
    (net (code "47") (name "Net-(U$9-ADDR)") (class "Default")
      (node (ref "U$12") (pin "2") (pinfunction "2_2") (pintype "passive"))
      (node (ref "U$9") (pin "P$1") (pinfunction "ADDR_P$1") (pintype "input"))
    )
    (net (code "48") (name "Net-(U$9-AIN0)") (class "Default")
      (node (ref "U$11") (pin "V-") (pinfunction "V-_V-") (pintype "bidirectional"))
      (node (ref "U$9") (pin "P$4") (pinfunction "AIN0_P$4") (pintype "input"))
    )
    (net (code "49") (name "Net-(U$10-A)") (class "Default")
      (node (ref "R_REF_6") (pin "2") (pinfunction "2_2") (pintype "passive"))
      (node (ref "U$10") (pin "P$3") (pinfunction "A_P$3") (pintype "passive"))
    )
    (net (code "50") (name "Net-(U$10-E)") (class "Default")
      (node (ref "R_REF_5") (pin "1") (pinfunction "1_1") (pintype "passive"))
      (node (ref "U$10") (pin "P$2") (pinfunction "E_P$2") (pintype "passive"))
    )
    (net (code "51") (name "Net-(U$10-S)") (class "Default")
      (node (ref "U$10") (pin "P$1") (pinfunction "S_P$1") (pintype "passive"))
      (node (ref "U$9") (pin "P$5") (pinfunction "AIN1_P$5") (pintype "input"))
    )
    (net (code "52") (name "Net-(U$13-ADDR)") (class "Default")
      (node (ref "U$13") (pin "P$1") (pinfunction "ADDR_P$1") (pintype "input"))
      (node (ref "U$16") (pin "2") (pinfunction "2_2") (pintype "passive"))
    )
    (net (code "53") (name "Net-(U$13-AIN0)") (class "Default")
      (node (ref "U$13") (pin "P$4") (pinfunction "AIN0_P$4") (pintype "input"))
      (node (ref "U$15") (pin "V-") (pinfunction "V-_V-") (pintype "bidirectional"))
    )
    (net (code "54") (name "Net-(U$13-AIN1)") (class "Default")
      (node (ref "U$13") (pin "P$5") (pinfunction "AIN1_P$5") (pintype "input"))
      (node (ref "U$14") (pin "P$1") (pinfunction "S_P$1") (pintype "passive"))
    )
    (net (code "55") (name "Net-(U$14-A)") (class "Default")
      (node (ref "R_REF_8") (pin "2") (pinfunction "2_2") (pintype "passive"))
      (node (ref "U$14") (pin "P$3") (pinfunction "A_P$3") (pintype "passive"))
    )
    (net (code "56") (name "Net-(U$14-E)") (class "Default")
      (node (ref "R_REF_7") (pin "1") (pinfunction "1_1") (pintype "passive"))
      (node (ref "U$14") (pin "P$2") (pinfunction "E_P$2") (pintype "passive"))
    )
    (net (code "57") (name "Net-(U$21-ADDR)") (class "Default")
      (node (ref "U$21") (pin "P$1") (pinfunction "ADDR_P$1") (pintype "input"))
      (node (ref "U$24") (pin "2") (pinfunction "2_2") (pintype "passive"))
    )
    (net (code "58") (name "Net-(U$21-AIN0)") (class "Default")
      (node (ref "U$21") (pin "P$4") (pinfunction "AIN0_P$4") (pintype "input"))
      (node (ref "U$23") (pin "V-") (pinfunction "V-_V-") (pintype "bidirectional"))
    )
    (net (code "59") (name "Net-(U$21-AIN1)") (class "Default")
      (node (ref "U$21") (pin "P$5") (pinfunction "AIN1_P$5") (pintype "input"))
      (node (ref "U$22") (pin "P$1") (pinfunction "S_P$1") (pintype "passive"))
    )
    (net (code "60") (name "Net-(U$22-A)") (class "Default")
      (node (ref "R_REF_12") (pin "2") (pinfunction "2_2") (pintype "passive"))
      (node (ref "U$22") (pin "P$3") (pinfunction "A_P$3") (pintype "passive"))
    )
    (net (code "61") (name "Net-(U$22-E)") (class "Default")
      (node (ref "R_REF_11") (pin "1") (pinfunction "1_1") (pintype "passive"))
      (node (ref "U$22") (pin "P$2") (pinfunction "E_P$2") (pintype "passive"))
    )
    (net (code "62") (name "Net-(U$25-ADDR)") (class "Default")
      (node (ref "U$25") (pin "P$1") (pinfunction "ADDR_P$1") (pintype "input"))
      (node (ref "U$28") (pin "2") (pinfunction "2_2") (pintype "passive"))
    )
    (net (code "63") (name "Net-(U$25-AIN0)") (class "Default")
      (node (ref "U$25") (pin "P$4") (pinfunction "AIN0_P$4") (pintype "input"))
      (node (ref "U$27") (pin "V-") (pinfunction "V-_V-") (pintype "bidirectional"))
    )
    (net (code "64") (name "Net-(U$25-AIN1)") (class "Default")
      (node (ref "U$25") (pin "P$5") (pinfunction "AIN1_P$5") (pintype "input"))
      (node (ref "U$26") (pin "P$1") (pinfunction "S_P$1") (pintype "passive"))
    )
    (net (code "65") (name "Net-(U$26-A)") (class "Default")
      (node (ref "R_REF_14") (pin "2") (pinfunction "2_2") (pintype "passive"))
      (node (ref "U$26") (pin "P$3") (pinfunction "A_P$3") (pintype "passive"))
    )
    (net (code "66") (name "Net-(U$26-E)") (class "Default")
      (node (ref "R_REF_13") (pin "1") (pinfunction "1_1") (pintype "passive"))
      (node (ref "U$26") (pin "P$2") (pinfunction "E_P$2") (pintype "passive"))
    )
    (net (code "67") (name "Net-(U$33-ADDR)") (class "Default")
      (node (ref "U$33") (pin "P$1") (pinfunction "ADDR_P$1") (pintype "input"))
      (node (ref "U$36") (pin "2") (pinfunction "2_2") (pintype "passive"))
    )
    (net (code "68") (name "Net-(U$33-AIN0)") (class "Default")
      (node (ref "U$33") (pin "P$4") (pinfunction "AIN0_P$4") (pintype "input"))
      (node (ref "U$35") (pin "V-") (pinfunction "V-_V-") (pintype "bidirectional"))
    )
    (net (code "69") (name "Net-(U$33-AIN1)") (class "Default")
      (node (ref "U$33") (pin "P$5") (pinfunction "AIN1_P$5") (pintype "input"))
      (node (ref "U$34") (pin "P$1") (pinfunction "S_P$1") (pintype "passive"))
    )
    (net (code "70") (name "Net-(U$34-A)") (class "Default")
      (node (ref "R_REF_18") (pin "2") (pinfunction "2_2") (pintype "passive"))
      (node (ref "U$34") (pin "P$3") (pinfunction "A_P$3") (pintype "passive"))
    )
    (net (code "71") (name "Net-(U$34-E)") (class "Default")
      (node (ref "R_REF_17") (pin "1") (pinfunction "1_1") (pintype "passive"))
      (node (ref "U$34") (pin "P$2") (pinfunction "E_P$2") (pintype "passive"))
    )
    (net (code "72") (name "Net-(U$41-ADDR)") (class "Default")
      (node (ref "U$41") (pin "P$1") (pinfunction "ADDR_P$1") (pintype "input"))
      (node (ref "U$44") (pin "2") (pinfunction "2_2") (pintype "passive"))
    )
    (net (code "73") (name "Net-(U$41-AIN0)") (class "Default")
      (node (ref "U$41") (pin "P$4") (pinfunction "AIN0_P$4") (pintype "input"))
      (node (ref "U$43") (pin "V-") (pinfunction "V-_V-") (pintype "bidirectional"))
    )
    (net (code "74") (name "Net-(U$41-AIN1)") (class "Default")
      (node (ref "U$41") (pin "P$5") (pinfunction "AIN1_P$5") (pintype "input"))
      (node (ref "U$42") (pin "P$1") (pinfunction "S_P$1") (pintype "passive"))
    )
    (net (code "75") (name "Net-(U$42-A)") (class "Default")
      (node (ref "R_REF_22") (pin "2") (pinfunction "2_2") (pintype "passive"))
      (node (ref "U$42") (pin "P$3") (pinfunction "A_P$3") (pintype "passive"))
    )
    (net (code "76") (name "Net-(U$42-E)") (class "Default")
      (node (ref "R_REF_21") (pin "1") (pinfunction "1_1") (pintype "passive"))
      (node (ref "U$42") (pin "P$2") (pinfunction "E_P$2") (pintype "passive"))
    )
    (net (code "77") (name "Net-(U$49-ADDR)") (class "Default")
      (node (ref "U$49") (pin "P$1") (pinfunction "ADDR_P$1") (pintype "input"))
      (node (ref "U$52") (pin "2") (pinfunction "2_2") (pintype "passive"))
    )
    (net (code "78") (name "Net-(U$49-AIN0)") (class "Default")
      (node (ref "U$49") (pin "P$4") (pinfunction "AIN0_P$4") (pintype "input"))
      (node (ref "U$51") (pin "V-") (pinfunction "V-_V-") (pintype "bidirectional"))
    )
    (net (code "79") (name "Net-(U$49-AIN1)") (class "Default")
      (node (ref "U$49") (pin "P$5") (pinfunction "AIN1_P$5") (pintype "input"))
      (node (ref "U$50") (pin "P$1") (pinfunction "S_P$1") (pintype "passive"))
    )
    (net (code "80") (name "Net-(U$50-A)") (class "Default")
      (node (ref "R_REF_26") (pin "2") (pinfunction "2_2") (pintype "passive"))
      (node (ref "U$50") (pin "P$3") (pinfunction "A_P$3") (pintype "passive"))
    )
    (net (code "81") (name "Net-(U$50-E)") (class "Default")
      (node (ref "R_REF_25") (pin "1") (pinfunction "1_1") (pintype "passive"))
      (node (ref "U$50") (pin "P$2") (pinfunction "E_P$2") (pintype "passive"))
    )
    (net (code "82") (name "VDD") (class "Default")
      (node (ref "C1") (pin "1") (pinfunction "1_1") (pintype "passive"))
      (node (ref "C11") (pin "1") (pinfunction "1_1") (pintype "passive"))
      (node (ref "C13") (pin "1") (pinfunction "1_1") (pintype "passive"))
      (node (ref "C3") (pin "1") (pinfunction "1_1") (pintype "passive"))
      (node (ref "C4") (pin "1") (pinfunction "1_1") (pintype "passive"))
      (node (ref "C6") (pin "1") (pinfunction "1_1") (pintype "passive"))
      (node (ref "C7") (pin "1") (pinfunction "1_1") (pintype "passive"))
      (node (ref "C9") (pin "1") (pinfunction "1_1") (pintype "passive"))
      (node (ref "U$1") (pin "P$8") (pinfunction "VDD_P$8") (pintype "power_in"))
      (node (ref "U$12") (pin "3") (pinfunction "3_3") (pintype "passive"))
      (node (ref "U$13") (pin "P$8") (pinfunction "VDD_P$8") (pintype "power_in"))
      (node (ref "U$16") (pin "3") (pinfunction "3_3") (pintype "passive"))
      (node (ref "U$21") (pin "P$8") (pinfunction "VDD_P$8") (pintype "power_in"))
      (node (ref "U$24") (pin "3") (pinfunction "3_3") (pintype "passive"))
      (node (ref "U$25") (pin "P$8") (pinfunction "VDD_P$8") (pintype "power_in"))
      (node (ref "U$28") (pin "3") (pinfunction "3_3") (pintype "passive"))
      (node (ref "U$33") (pin "P$8") (pinfunction "VDD_P$8") (pintype "power_in"))
      (node (ref "U$36") (pin "3") (pinfunction "3_3") (pintype "passive"))
      (node (ref "U$41") (pin "P$8") (pinfunction "VDD_P$8") (pintype "power_in"))
      (node (ref "U$44") (pin "3") (pinfunction "3_3") (pintype "passive"))
      (node (ref "U$49") (pin "P$8") (pinfunction "VDD_P$8") (pintype "power_in"))
      (node (ref "U$5") (pin "3") (pinfunction "3_3") (pintype "passive"))
      (node (ref "U$52") (pin "3") (pinfunction "3_3") (pintype "passive"))
      (node (ref "U$9") (pin "P$8") (pinfunction "VDD_P$8") (pintype "power_in"))
      (node (ref "VDD") (pin "1") (pinfunction "P_1") (pintype "passive"))
      (node (ref "VDD10") (pin "1") (pinfunction "P_1") (pintype "passive"))
      (node (ref "VDD12") (pin "1") (pinfunction "P_1") (pintype "passive"))
      (node (ref "VDD2") (pin "1") (pinfunction "P_1") (pintype "passive"))
      (node (ref "VDD3") (pin "1") (pinfunction "P_1") (pintype "passive"))
      (node (ref "VDD5") (pin "1") (pinfunction "P_1") (pintype "passive"))
      (node (ref "VDD6") (pin "1") (pinfunction "P_1") (pintype "passive"))
      (node (ref "VDD8") (pin "1") (pinfunction "P_1") (pintype "passive"))
    )
    (net (code "83") (name "unconnected-(U$1-AIN2-PadP$6)") (class "Default")
      (node (ref "U$1") (pin "P$6") (pinfunction "AIN2_P$6") (pintype "input"))
    )
    (net (code "84") (name "unconnected-(U$1-AIN3-PadP$7)") (class "Default")
      (node (ref "U$1") (pin "P$7") (pinfunction "AIN3_P$7") (pintype "input"))
    )
    (net (code "85") (name "unconnected-(U$1-ALERT-PadP$2)") (class "Default")
      (node (ref "U$1") (pin "P$2") (pinfunction "ALERT_P$2") (pintype "output"))
    )
    (net (code "86") (name "unconnected-(U$9-AIN2-PadP$6)") (class "Default")
      (node (ref "U$9") (pin "P$6") (pinfunction "AIN2_P$6") (pintype "input"))
    )
    (net (code "87") (name "unconnected-(U$9-AIN3-PadP$7)") (class "Default")
      (node (ref "U$9") (pin "P$7") (pinfunction "AIN3_P$7") (pintype "input"))
    )
    (net (code "88") (name "unconnected-(U$9-ALERT-PadP$2)") (class "Default")
      (node (ref "U$9") (pin "P$2") (pinfunction "ALERT_P$2") (pintype "output"))
    )
    (net (code "89") (name "unconnected-(U$13-AIN2-PadP$6)") (class "Default")
      (node (ref "U$13") (pin "P$6") (pinfunction "AIN2_P$6") (pintype "input"))
    )
    (net (code "90") (name "unconnected-(U$13-AIN3-PadP$7)") (class "Default")
      (node (ref "U$13") (pin "P$7") (pinfunction "AIN3_P$7") (pintype "input"))
    )
    (net (code "91") (name "unconnected-(U$13-ALERT-PadP$2)") (class "Default")
      (node (ref "U$13") (pin "P$2") (pinfunction "ALERT_P$2") (pintype "output"))
    )
    (net (code "92") (name "unconnected-(U$21-AIN2-PadP$6)") (class "Default")
      (node (ref "U$21") (pin "P$6") (pinfunction "AIN2_P$6") (pintype "input"))
    )
    (net (code "93") (name "unconnected-(U$21-AIN3-PadP$7)") (class "Default")
      (node (ref "U$21") (pin "P$7") (pinfunction "AIN3_P$7") (pintype "input"))
    )
    (net (code "94") (name "unconnected-(U$21-ALERT-PadP$2)") (class "Default")
      (node (ref "U$21") (pin "P$2") (pinfunction "ALERT_P$2") (pintype "output"))
    )
    (net (code "95") (name "unconnected-(U$25-AIN2-PadP$6)") (class "Default")
      (node (ref "U$25") (pin "P$6") (pinfunction "AIN2_P$6") (pintype "input"))
    )
    (net (code "96") (name "unconnected-(U$25-AIN3-PadP$7)") (class "Default")
      (node (ref "U$25") (pin "P$7") (pinfunction "AIN3_P$7") (pintype "input"))
    )
    (net (code "97") (name "unconnected-(U$25-ALERT-PadP$2)") (class "Default")
      (node (ref "U$25") (pin "P$2") (pinfunction "ALERT_P$2") (pintype "output"))
    )
    (net (code "98") (name "unconnected-(U$33-AIN2-PadP$6)") (class "Default")
      (node (ref "U$33") (pin "P$6") (pinfunction "AIN2_P$6") (pintype "input"))
    )
    (net (code "99") (name "unconnected-(U$33-AIN3-PadP$7)") (class "Default")
      (node (ref "U$33") (pin "P$7") (pinfunction "AIN3_P$7") (pintype "input"))
    )
    (net (code "100") (name "unconnected-(U$33-ALERT-PadP$2)") (class "Default")
      (node (ref "U$33") (pin "P$2") (pinfunction "ALERT_P$2") (pintype "output"))
    )
    (net (code "101") (name "unconnected-(U$41-AIN2-PadP$6)") (class "Default")
      (node (ref "U$41") (pin "P$6") (pinfunction "AIN2_P$6") (pintype "input"))
    )
    (net (code "102") (name "unconnected-(U$41-AIN3-PadP$7)") (class "Default")
      (node (ref "U$41") (pin "P$7") (pinfunction "AIN3_P$7") (pintype "input"))
    )
    (net (code "103") (name "unconnected-(U$41-ALERT-PadP$2)") (class "Default")
      (node (ref "U$41") (pin "P$2") (pinfunction "ALERT_P$2") (pintype "output"))
    )
    (net (code "104") (name "unconnected-(U$49-AIN2-PadP$6)") (class "Default")
      (node (ref "U$49") (pin "P$6") (pinfunction "AIN2_P$6") (pintype "input"))
    )
    (net (code "105") (name "unconnected-(U$49-AIN3-PadP$7)") (class "Default")
      (node (ref "U$49") (pin "P$7") (pinfunction "AIN3_P$7") (pintype "input"))
    )
    (net (code "106") (name "unconnected-(U$49-ALERT-PadP$2)") (class "Default")
      (node (ref "U$49") (pin "P$2") (pinfunction "ALERT_P$2") (pintype "output"))
    )
  )
)
